# highvoltage.net
KiCad netlist of a schematic drawn in EAGLE
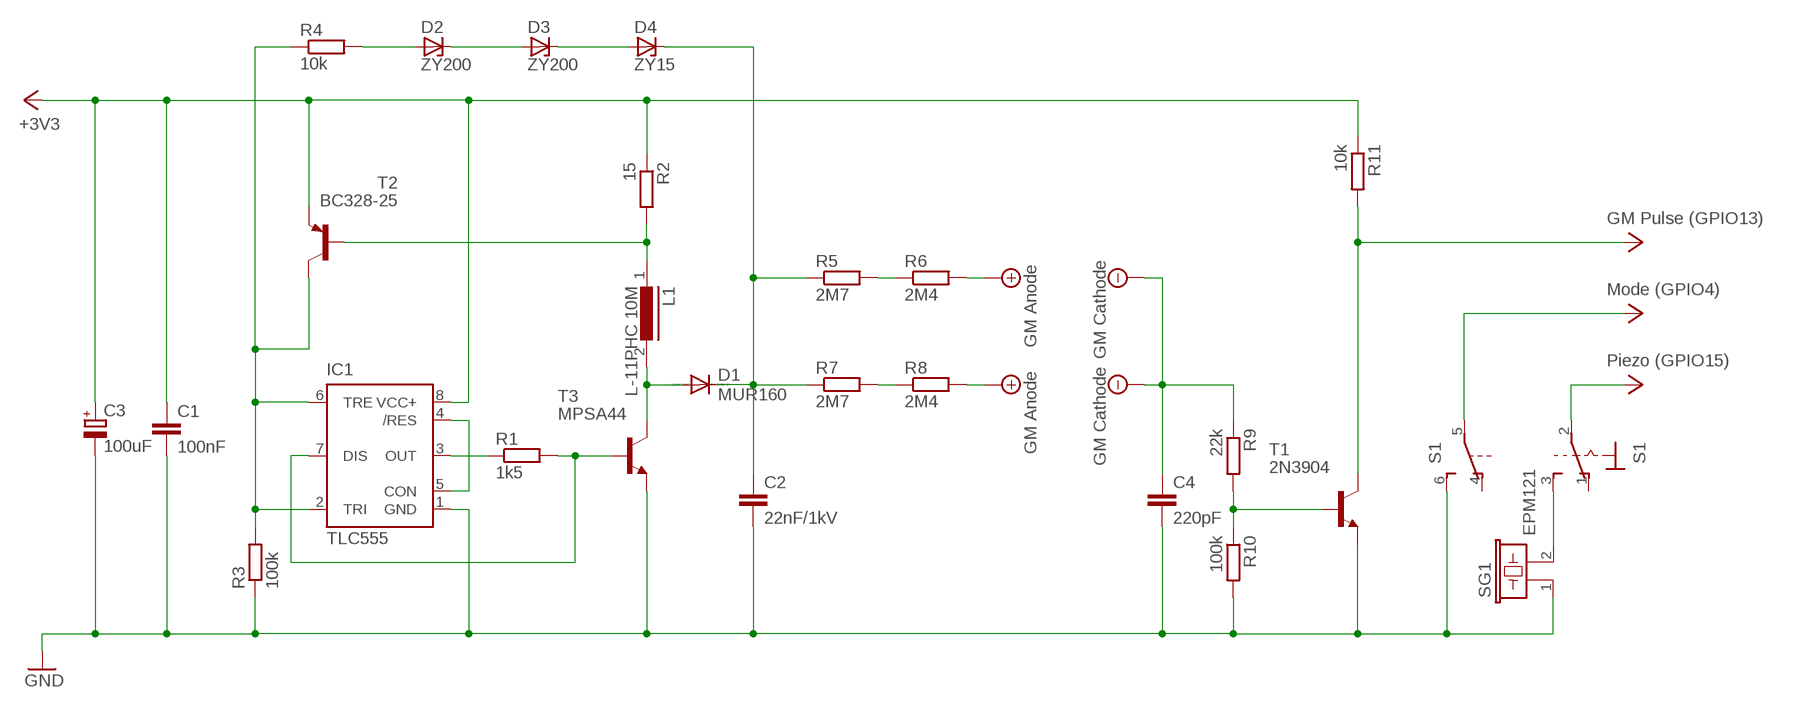
[diagram p0: schematic, sheet 1]

(export (version "E")
  (design (tool "Eeschema 10.0.6"))
  (components
    (comp (ref "C1")
      (value "100nF")
      (footprint "eagle-import:C2.5-2")
      (libsource (lib "eagle-import") (part "C2.5/2"))
    )
    (comp (ref "C2")
      (value "22nF/1kV")
      (footprint "eagle-import:C15B5")
      (libsource (lib "eagle-import") (part "C15/5"))
    )
    (comp (ref "C3")
      (value "100uF")
      (footprint "eagle-import:E2-5")
      (libsource (lib "eagle-import") (part "CPOL-EUE2-5"))
    )
    (comp (ref "C4")
      (value "220pF")
      (footprint "eagle-import:C7.5B3")
      (libsource (lib "eagle-import") (part "C7.5/3"))
    )
    (comp (ref "D1")
      (value "MUR160")
      (footprint "eagle-import:DO41-10")
      (libsource (lib "eagle-import") (part "MUR150RL"))
    )
    (comp (ref "D2")
      (value "ZY200")
      (footprint "eagle-import:P1Z12")
      (libsource (lib "eagle-import") (part "ZY"))
    )
    (comp (ref "D3")
      (value "ZY200")
      (footprint "eagle-import:P1Z12")
      (libsource (lib "eagle-import") (part "ZY"))
    )
    (comp (ref "D4")
      (value "ZY15")
      (footprint "eagle-import:DO13M")
      (libsource (lib "eagle-import") (part "ZDXX"))
    )
    (comp (ref "IC1")
      (value "TLC555")
      (footprint "eagle-import:DIL-08")
      (fields (field (name "MF") "Arrow Electronics") (field (name "MPN") "NE555N"))
      (libsource (lib "eagle-import") (part "NE555"))
    )
    (comp (ref "L1")
      (value "L-11PHC 10M")
      (footprint "eagle-import:82114R")
      (libsource (lib "eagle-import") (part "82114R"))
    )
    (comp (ref "R1")
      (value "1k5")
      (footprint "eagle-import:0204_7")
      (libsource (lib "eagle-import") (part "R-EU_0204/7"))
    )
    (comp (ref "R2")
      (value "15")
      (footprint "eagle-import:0204_7")
      (libsource (lib "eagle-import") (part "R-EU_0204/7"))
    )
    (comp (ref "R3")
      (value "100k")
      (footprint "eagle-import:0204_7")
      (libsource (lib "eagle-import") (part "R-EU_0204/7"))
    )
    (comp (ref "R4")
      (value "10k")
      (footprint "eagle-import:0204_7")
      (libsource (lib "eagle-import") (part "R-EU_0204/7"))
    )
    (comp (ref "R5")
      (value "2M7")
      (footprint "eagle-import:0204_7")
      (libsource (lib "eagle-import") (part "R-EU_0204/7"))
    )
    (comp (ref "R6")
      (value "2M4")
      (footprint "eagle-import:0204_7")
      (libsource (lib "eagle-import") (part "R-EU_0204/7"))
    )
    (comp (ref "R7")
      (value "2M7")
      (footprint "eagle-import:0204_7")
      (libsource (lib "eagle-import") (part "R-EU_0204/7"))
    )
    (comp (ref "R8")
      (value "2M4")
      (footprint "eagle-import:0204_7")
      (libsource (lib "eagle-import") (part "R-EU_0204/7"))
    )
    (comp (ref "R9")
      (value "22k")
      (footprint "eagle-import:0204_7")
      (libsource (lib "eagle-import") (part "R-EU_0204/7"))
    )
    (comp (ref "R10")
      (value "100k")
      (footprint "eagle-import:0204_7")
      (libsource (lib "eagle-import") (part "R-EU_0204/7"))
    )
    (comp (ref "R11")
      (value "10k")
      (footprint "eagle-import:0204_7")
      (libsource (lib "eagle-import") (part "R-EU_0204/7"))
    )
    (comp (ref "S1")
      (value "320-938")
      (footprint "eagle-import:320-938")
      (libsource (lib "eagle-import") (part "320-938"))
    )
    (comp (ref "SG1")
      (value "EPM121")
      (footprint "eagle-import:EFBAA40D101")
      (libsource (lib "eagle-import") (part "EFB?AA40D101"))
    )
    (comp (ref "T1")
      (value "2N3904")
      (footprint "eagle-import:TO92")
      (libsource (lib "eagle-import") (part "2N3904"))
    )
    (comp (ref "T2")
      (value "BC328-25")
      (footprint "eagle-import:TO92-EBC")
      (libsource (lib "eagle-import") (part "BC328-25"))
    )
    (comp (ref "T3")
      (value "MPSA44")
      (footprint "eagle-import:TO92-EBC")
      (libsource (lib "eagle-import") (part "-NPN-TO92-EBCMPSA44"))
    )
  )
  (nets
    (net (code "1") (name "+3V3") (class "Default")
      (node (ref "C1") (pin "1") (pinfunction "1_1") (pintype "passive"))
      (node (ref "C3") (pin "+") (pinfunction "+_+") (pintype "passive"))
      (node (ref "IC1") (pin "8") (pinfunction "VCC+_8") (pintype "power_in"))
      (node (ref "R11") (pin "1") (pinfunction "1_1") (pintype "passive"))
      (node (ref "R11") (pin "2") (pinfunction "2_2") (pintype "passive"))
      (node (ref "R2") (pin "1") (pinfunction "1_1") (pintype "passive"))
      (node (ref "S1") (pin "2") (pinfunction "P_2") (pintype "passive"))
      (node (ref "T1") (pin "1") (pinfunction "C_1") (pintype "passive"))
      (node (ref "T2") (pin "E") (pinfunction "E_E") (pintype "passive"))
    )
    (net (code "2") (name "GM Anode") (class "Default")
      (node (ref "R6") (pin "2") (pinfunction "2_2") (pintype "passive"))
      (node (ref "R8") (pin "2") (pinfunction "2_2") (pintype "passive"))
    )
    (net (code "3") (name "GM Cathode") (class "Default")
      (node (ref "C4") (pin "1") (pinfunction "1_1") (pintype "passive"))
      (node (ref "R9") (pin "1") (pinfunction "1_1") (pintype "passive"))
    )
    (net (code "4") (name "GND") (class "Default")
      (node (ref "C1") (pin "2") (pinfunction "2_2") (pintype "passive"))
      (node (ref "C2") (pin "2") (pinfunction "2_2") (pintype "passive"))
      (node (ref "C3") (pin "-") (pinfunction "-_-") (pintype "passive"))
      (node (ref "C4") (pin "2") (pinfunction "2_2") (pintype "passive"))
      (node (ref "IC1") (pin "1") (pinfunction "GND_1") (pintype "power_in"))
      (node (ref "R10") (pin "2") (pinfunction "2_2") (pintype "passive"))
      (node (ref "R3") (pin "1") (pinfunction "1_1") (pintype "passive"))
      (node (ref "S1") (pin "6") (pinfunction "S_6") (pintype "passive"))
      (node (ref "SG1") (pin "1") (pinfunction "1_1") (pintype "passive"))
      (node (ref "T1") (pin "3") (pinfunction "E_3") (pintype "passive"))
      (node (ref "T3") (pin "E") (pinfunction "E_E") (pintype "passive"))
    )
    (net (code "5") (name "Mode (GPIO4)") (class "Default")
      (node (ref "S1") (pin "5") (pinfunction "P_5") (pintype "passive"))
    )
    (net (code "6") (name "Net-(C2-Pad1)") (class "Default")
      (node (ref "C2") (pin "1") (pinfunction "1_1") (pintype "passive"))
      (node (ref "D1") (pin "C") (pinfunction "C_C") (pintype "passive"))
      (node (ref "D4") (pin "C") (pinfunction "C_C") (pintype "passive"))
      (node (ref "R5") (pin "1") (pinfunction "1_1") (pintype "passive"))
      (node (ref "R7") (pin "1") (pinfunction "1_1") (pintype "passive"))
    )
    (net (code "7") (name "Net-(D1-PadA)") (class "Default")
      (node (ref "D1") (pin "A") (pinfunction "A_A") (pintype "passive"))
      (node (ref "L1") (pin "2") (pinfunction "2_2") (pintype "passive"))
      (node (ref "T3") (pin "C") (pinfunction "C_C") (pintype "passive"))
    )
    (net (code "8") (name "Net-(D2-PadA)") (class "Default")
      (node (ref "D2") (pin "A") (pinfunction "A_A") (pintype "passive"))
      (node (ref "R4") (pin "2") (pinfunction "2_2") (pintype "passive"))
    )
    (net (code "9") (name "Net-(D2-PadC)") (class "Default")
      (node (ref "D2") (pin "C") (pinfunction "C_C") (pintype "passive"))
      (node (ref "D3") (pin "A") (pinfunction "A_A") (pintype "passive"))
    )
    (net (code "10") (name "Net-(D3-PadC)") (class "Default")
      (node (ref "D3") (pin "C") (pinfunction "C_C") (pintype "passive"))
      (node (ref "D4") (pin "A") (pinfunction "A_A") (pintype "passive"))
    )
    (net (code "11") (name "Net-(IC1-CON)") (class "Default")
      (node (ref "IC1") (pin "4") (pinfunction "/RES_4") (pintype "input"))
      (node (ref "IC1") (pin "5") (pinfunction "CON_5") (pintype "input"))
    )
    (net (code "12") (name "Net-(IC1-DIS)") (class "Default")
      (node (ref "IC1") (pin "7") (pinfunction "DIS_7") (pintype "input"))
      (node (ref "R1") (pin "2") (pinfunction "2_2") (pintype "passive"))
      (node (ref "T3") (pin "B") (pinfunction "B_B") (pintype "passive"))
    )
    (net (code "13") (name "Net-(IC1-OUT)") (class "Default")
      (node (ref "IC1") (pin "3") (pinfunction "OUT_3") (pintype "output"))
      (node (ref "R1") (pin "1") (pinfunction "1_1") (pintype "passive"))
    )
    (net (code "14") (name "Net-(IC1-TRE)") (class "Default")
      (node (ref "IC1") (pin "2") (pinfunction "TRI_2") (pintype "input"))
      (node (ref "IC1") (pin "6") (pinfunction "TRE_6") (pintype "input"))
      (node (ref "R3") (pin "2") (pinfunction "2_2") (pintype "passive"))
      (node (ref "R4") (pin "1") (pinfunction "1_1") (pintype "passive"))
      (node (ref "T2") (pin "C") (pinfunction "C_C") (pintype "passive"))
    )
    (net (code "15") (name "Net-(L1-Pad1)") (class "Default")
      (node (ref "L1") (pin "1") (pinfunction "1_1") (pintype "passive"))
      (node (ref "R2") (pin "2") (pinfunction "2_2") (pintype "passive"))
      (node (ref "T2") (pin "B") (pinfunction "B_B") (pintype "passive"))
    )
    (net (code "16") (name "Net-(R5-Pad2)") (class "Default")
      (node (ref "R5") (pin "2") (pinfunction "2_2") (pintype "passive"))
      (node (ref "R6") (pin "1") (pinfunction "1_1") (pintype "passive"))
    )
    (net (code "17") (name "Net-(R7-Pad2)") (class "Default")
      (node (ref "R7") (pin "2") (pinfunction "2_2") (pintype "passive"))
      (node (ref "R8") (pin "1") (pinfunction "1_1") (pintype "passive"))
    )
    (net (code "18") (name "Net-(S1A-S)") (class "Default")
      (node (ref "S1") (pin "3") (pinfunction "S_3") (pintype "passive"))
      (node (ref "SG1") (pin "2") (pinfunction "2_2") (pintype "passive"))
    )
    (net (code "19") (name "Net-(T1-B)") (class "Default")
      (node (ref "R10") (pin "1") (pinfunction "1_1") (pintype "passive"))
      (node (ref "R9") (pin "2") (pinfunction "2_2") (pintype "passive"))
      (node (ref "T1") (pin "2") (pinfunction "B_2") (pintype "passive"))
    )
    (net (code "20") (name "unconnected-(S1A-O-Pad1)") (class "Default")
      (node (ref "S1") (pin "1") (pinfunction "O_1") (pintype "passive"))
    )
    (net (code "21") (name "unconnected-(S1B-O-Pad4)") (class "Default")
      (node (ref "S1") (pin "4") (pinfunction "O_4") (pintype "passive"))
    )
  )
)
